# Threeno_Tiny_Tx_Rev1B.net
KiCad netlist of a schematic drawn in EAGLE
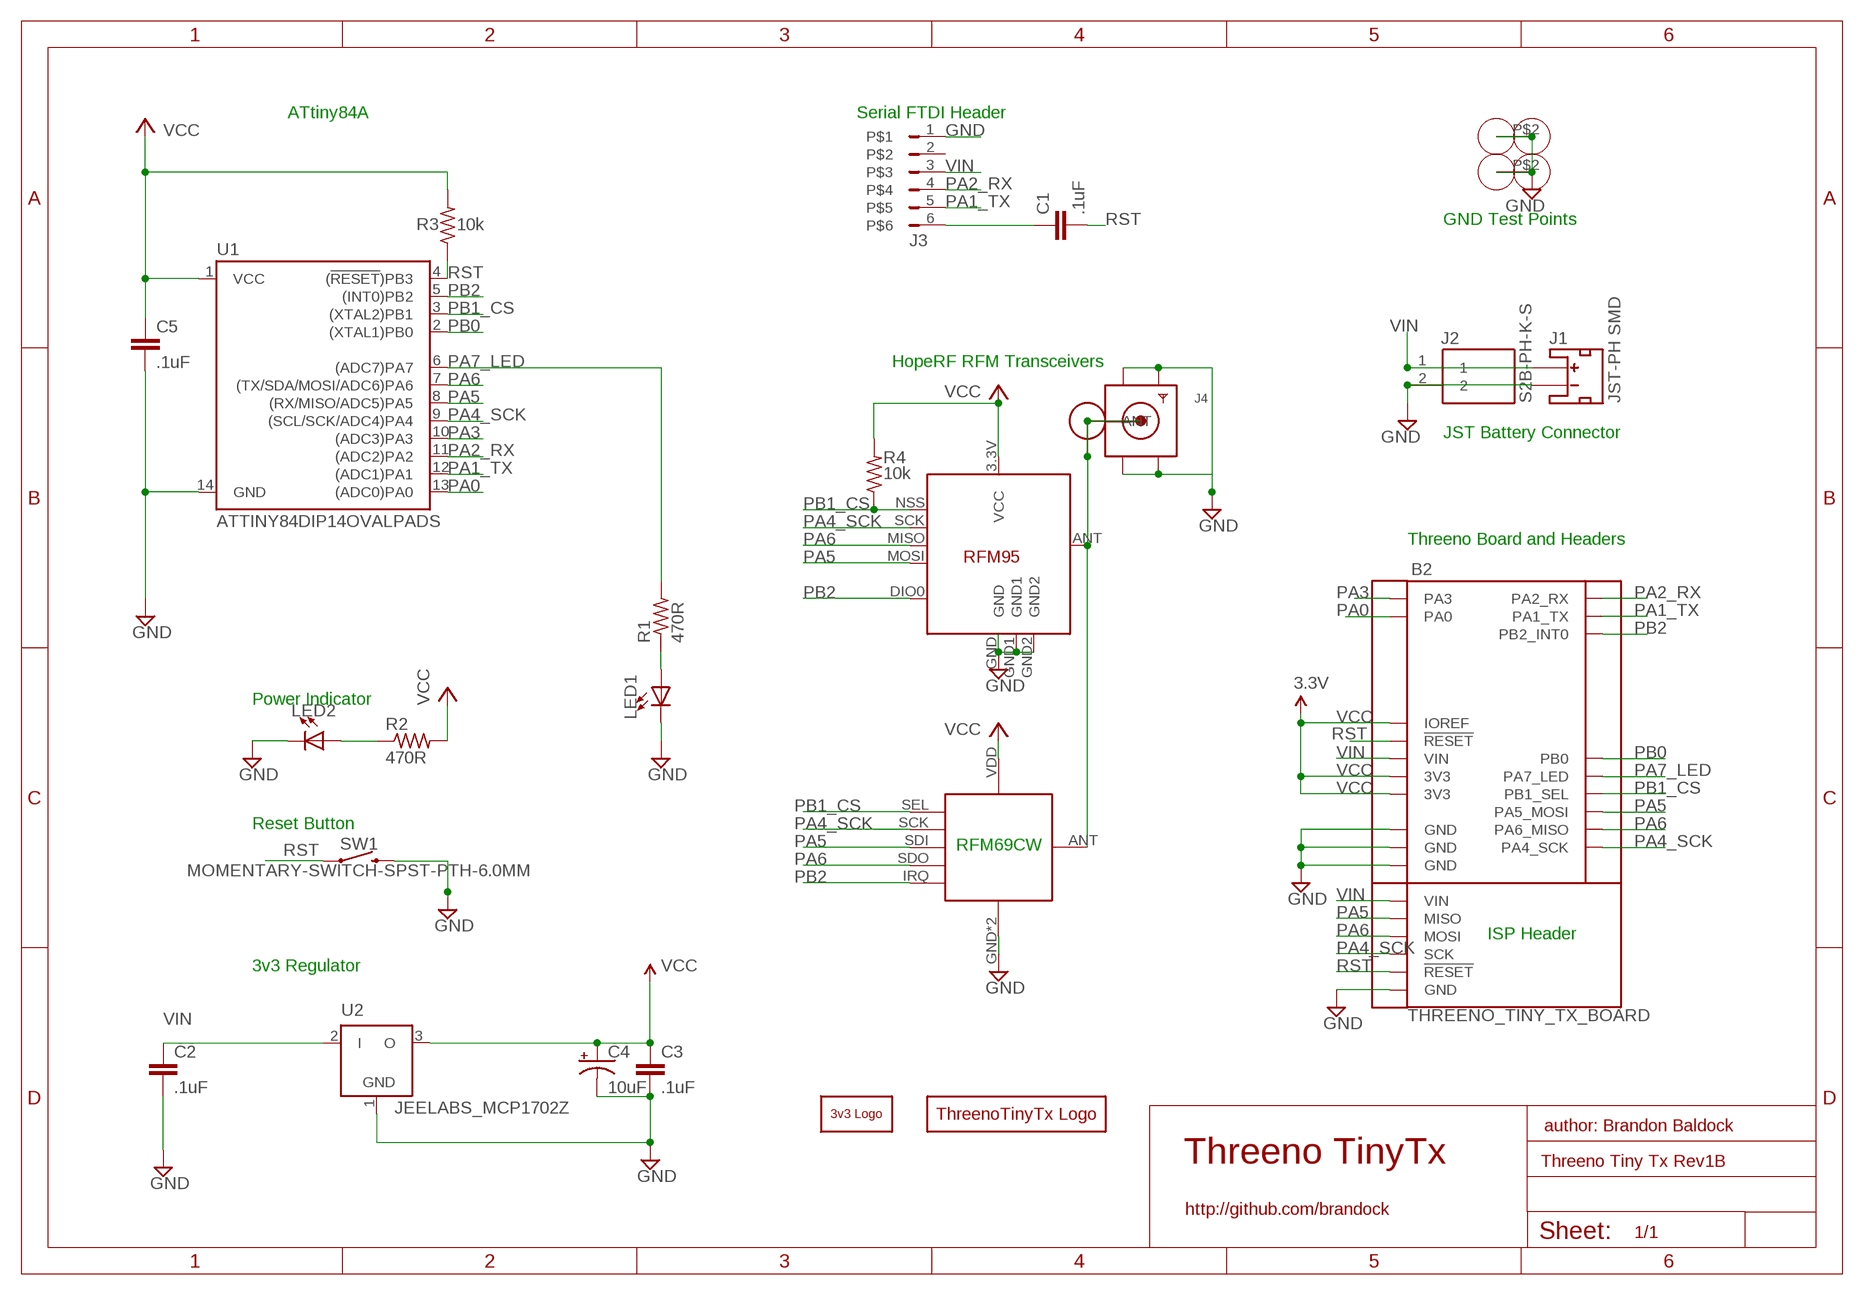
[diagram p0: schematic, sheet 1]

(export (version "E")
  (design (tool "Eeschema 10.0.6"))
  (components
    (comp (ref "B1")
      (value "3VTHREENO_BOTTOM_SILK")
      (footprint "eagle-import:3VTHREENO_BOTTOM_SILK")
      (libsource (lib "eagle-import") (part "3VTHREENO_BOTTOM_SILK"))
    )
    (comp (ref "B2")
      (value "THREENO_TINY_TX_BOARD")
      (footprint "eagle-import:THREENO_TINY_TX_BOARD")
      (libsource (lib "eagle-import") (part "THREENO_TINY_TX_BOARD"))
    )
    (comp (ref "B3")
      (value "THREENO_TINY_TX_LOGOTHREENO_TINY_TX_LOGO")
      (footprint "eagle-import:THREENO_TINY_TX_LOGO")
      (libsource (lib "eagle-import") (part "THREENO_TINY_TX_LOGOTHREENO_TINY_TX_LOGO"))
    )
    (comp (ref "C1")
      (value ".1uF")
      (footprint "eagle-import:C025-024X044-NO-MIDDLE-SILK")
      (libsource (lib "eagle-import") (part "C-EU025-024X044-NO_MIDDLE_SILK"))
    )
    (comp (ref "C2")
      (value ".1uF")
      (footprint "eagle-import:C025-024X044-NO-MIDDLE-SILK")
      (libsource (lib "eagle-import") (part "C-EU025-024X044-NO_MIDDLE_SILK"))
    )
    (comp (ref "C3")
      (value ".1uF")
      (footprint "eagle-import:C025-024X044-NO-MIDDLE-SILK")
      (libsource (lib "eagle-import") (part "C-EU025-024X044-NO_MIDDLE_SILK"))
    )
    (comp (ref "C4")
      (value "10uF")
      (footprint "eagle-import:E1,8-4")
      (libsource (lib "eagle-import") (part "CPOL-USE1.8-4"))
    )
    (comp (ref "C5")
      (value ".1uF")
      (footprint "eagle-import:C025-024X044-NO-MIDDLE-SILK")
      (libsource (lib "eagle-import") (part "C-EU025-024X044-NO_MIDDLE_SILK"))
    )
    (comp (ref "J1")
      (value "JST_2MM_MALE")
      (footprint "eagle-import:JST-2-SMD")
      (libsource (lib "eagle-import") (part "JST_2MM_MALE"))
    )
    (comp (ref "J2")
      (value "S2B-PH-K-S")
      (footprint "eagle-import:S2BPHKS")
      (libsource (lib "eagle-import") (part "S2B-PH-K-S"))
    )
    (comp (ref "J3")
      (value "FTDI")
      (footprint "eagle-import:FTDI_ROUND_HEADER_SILK")
      (libsource (lib "eagle-import") (part "FTDI"))
    )
    (comp (ref "J4")
      (value "SMACONNECTOR_EDGE")
      (footprint "eagle-import:SMA_EDGELAUNCH")
      (libsource (lib "eagle-import") (part "SMACONNECTOR_EDGE"))
    )
    (comp (ref "J5")
      (value "RFM12B_ANTENNA")
      (footprint "eagle-import:RFM12B-ANTENNA")
      (libsource (lib "eagle-import") (part "RFM12B_ANTENNA"))
    )
    (comp (ref "J6")
      (value "ALLIGATORCLIP-WIRELOOPTESTPOINT-WIRELOOP")
      (footprint "eagle-import:ALLIGATORCLIP-WIRELOOP")
      (libsource (lib "eagle-import") (part "ALLIGATORCLIP-WIRELOOPTESTPOINT-WIRELOOP"))
    )
    (comp (ref "J7")
      (value "ALLIGATORCLIP-WIRELOOPTESTPOINT-WIRELOOP")
      (footprint "eagle-import:ALLIGATORCLIP-WIRELOOP")
      (libsource (lib "eagle-import") (part "ALLIGATORCLIP-WIRELOOPTESTPOINT-WIRELOOP"))
    )
    (comp (ref "LED1")
      (value "LED-BRANDOCK3MM")
      (footprint "eagle-import:LED3MM-BRANDOCK")
      (libsource (lib "eagle-import") (part "LED-BRANDOCK3MM"))
    )
    (comp (ref "LED2")
      (value "LED-BRANDOCK3MM")
      (footprint "eagle-import:LED3MM-BRANDOCK")
      (libsource (lib "eagle-import") (part "LED-BRANDOCK3MM"))
    )
    (comp (ref "R1")
      (value "470R")
      (footprint "eagle-import:0204_7")
      (libsource (lib "eagle-import") (part "R-US_0204/7"))
    )
    (comp (ref "R2")
      (value "470R")
      (footprint "eagle-import:0204_7")
      (libsource (lib "eagle-import") (part "R-US_0204/7"))
    )
    (comp (ref "R3")
      (value "10k")
      (footprint "eagle-import:0204_7")
      (libsource (lib "eagle-import") (part "R-US_0204/7"))
    )
    (comp (ref "R4")
      (value "10k")
      (footprint "eagle-import:0204_7")
      (libsource (lib "eagle-import") (part "R-US_0204/7"))
    )
    (comp (ref "RF1")
      (value "RFM12B_MINPADS")
      (footprint "eagle-import:RFM12B-MINPADS")
      (libsource (lib "eagle-import") (part "RFM12B_MINPADS"))
    )
    (comp (ref "RF2")
      (value "RFM95LONGER")
      (footprint "eagle-import:RFM95_LONGER")
      (libsource (lib "eagle-import") (part "RFM95LONGER"))
    )
    (comp (ref "SW1")
      (value "MOMENTARY-SWITCH-SPST-PTH-6.0MM")
      (footprint "eagle-import:TACTILE_SWITCH_PTH_6.0MM")
      (libsource (lib "eagle-import") (part "MOMENTARY-SWITCH-SPST-PTH-6.0MM"))
    )
    (comp (ref "U1")
      (value "ATTINY84DIP14OVALPADS")
      (footprint "eagle-import:DIP14-OVALPADS")
      (libsource (lib "eagle-import") (part "ATTINY84DIP14OVALPADS"))
    )
    (comp (ref "U2")
      (value "JEELABS_MCP1702Z")
      (footprint "eagle-import:JEELABS_TO92")
      (libsource (lib "eagle-import") (part "JEELABS_MCP1702Z"))
    )
  )
  (nets
    (net (code "1") (name "/PA0") (class "Default")
      (node (ref "B2") (pin "PA0") (pinfunction "PA0_PA0") (pintype "bidirectional"))
      (node (ref "U1") (pin "13") (pinfunction "(ADC0)PA0_13") (pintype "bidirectional"))
    )
    (net (code "2") (name "/PA1_TX") (class "Default")
      (node (ref "B2") (pin "PA1") (pinfunction "PA1_TX_PA1") (pintype "bidirectional"))
      (node (ref "J3") (pin "5") (pinfunction "P$5_5") (pintype "bidirectional"))
      (node (ref "U1") (pin "12") (pinfunction "(ADC1)PA1_12") (pintype "bidirectional"))
    )
    (net (code "3") (name "/PA2_RX") (class "Default")
      (node (ref "B2") (pin "PA2") (pinfunction "PA2_RX_PA2") (pintype "bidirectional"))
      (node (ref "J3") (pin "4") (pinfunction "P$4_4") (pintype "bidirectional"))
      (node (ref "U1") (pin "11") (pinfunction "(ADC2)PA2_11") (pintype "bidirectional"))
    )
    (net (code "4") (name "/PA3") (class "Default")
      (node (ref "B2") (pin "PA3") (pinfunction "PA3_PA3") (pintype "bidirectional"))
      (node (ref "U1") (pin "10") (pinfunction "(ADC3)PA3_10") (pintype "bidirectional"))
    )
    (net (code "5") (name "/PA4_SCK") (class "Default")
      (node (ref "B2") (pin "PA4") (pinfunction "PA4_SCK_PA4") (pintype "bidirectional"))
      (node (ref "B2") (pin "SCK@ICSP") (pinfunction "SCK_SCK@ICSP") (pintype "bidirectional"))
      (node (ref "RF1") (pin "SCK") (pinfunction "SCK_SCK") (pintype "bidirectional"))
      (node (ref "RF2") (pin "SCK") (pinfunction "SCK_SCK") (pintype "input"))
      (node (ref "U1") (pin "9") (pinfunction "(SCL/SCK/ADC4)PA4_9") (pintype "bidirectional"))
    )
    (net (code "6") (name "/PA5") (class "Default")
      (node (ref "B2") (pin "MISO@ICSP") (pinfunction "MISO_MISO@ICSP") (pintype "bidirectional"))
      (node (ref "B2") (pin "PA5") (pinfunction "PA5_MOSI_PA5") (pintype "bidirectional"))
      (node (ref "RF1") (pin "SDI") (pinfunction "SDI/MOSI_SDI") (pintype "bidirectional"))
      (node (ref "RF2") (pin "MOSI") (pinfunction "MOSI_MOSI") (pintype "output"))
      (node (ref "U1") (pin "8") (pinfunction "(RX/MISO/ADC5)PA5_8") (pintype "bidirectional"))
    )
    (net (code "7") (name "/PA6") (class "Default")
      (node (ref "B2") (pin "MOSI@ICSP") (pinfunction "MOSI_MOSI@ICSP") (pintype "bidirectional"))
      (node (ref "B2") (pin "PA6") (pinfunction "PA6_MISO_PA6") (pintype "bidirectional"))
      (node (ref "RF1") (pin "SDO") (pinfunction "SDO/MISO_SDO") (pintype "bidirectional"))
      (node (ref "RF2") (pin "MISO") (pinfunction "MISO_MISO") (pintype "input"))
      (node (ref "U1") (pin "7") (pinfunction "(TX/SDA/MOSI/ADC6)PA6_7") (pintype "bidirectional"))
    )
    (net (code "8") (name "/PA7_LED") (class "Default")
      (node (ref "B2") (pin "PA7") (pinfunction "PA7_LED_PA7") (pintype "bidirectional"))
      (node (ref "R1") (pin "2") (pinfunction "2_2") (pintype "passive"))
      (node (ref "U1") (pin "6") (pinfunction "(ADC7)PA7_6") (pintype "bidirectional"))
    )
    (net (code "9") (name "/PB0") (class "Default")
      (node (ref "B2") (pin "PB0") (pinfunction "PB0_PB0") (pintype "bidirectional"))
      (node (ref "U1") (pin "2") (pinfunction "(XTAL1)PB0_2") (pintype "bidirectional"))
    )
    (net (code "10") (name "/PB1_CS") (class "Default")
      (node (ref "B2") (pin "PB1") (pinfunction "PB1_SEL_PB1") (pintype "bidirectional"))
      (node (ref "R4") (pin "1") (pinfunction "1_1") (pintype "passive"))
      (node (ref "RF1") (pin "SEL") (pinfunction "SEL_SEL") (pintype "bidirectional"))
      (node (ref "RF2") (pin "NSS") (pinfunction "SEL_NSS") (pintype "input"))
      (node (ref "U1") (pin "3") (pinfunction "(XTAL2)PB1_3") (pintype "bidirectional"))
    )
    (net (code "11") (name "/PB2") (class "Default")
      (node (ref "B2") (pin "PB2") (pinfunction "PB2_INT0_PB2") (pintype "bidirectional"))
      (node (ref "RF1") (pin "IRQ") (pinfunction "IRQ_IRQ") (pintype "bidirectional"))
      (node (ref "RF2") (pin "DIO0") (pinfunction "DIO0_DIO0") (pintype "open_collector"))
      (node (ref "U1") (pin "5") (pinfunction "(INT0)PB2_5") (pintype "bidirectional"))
    )
    (net (code "12") (name "/RST") (class "Default")
      (node (ref "B2") (pin "!RESET!") (pinfunction "~{RESET}_!RESET!") (pintype "bidirectional"))
      (node (ref "B2") (pin "RESET@ICSP") (pinfunction "~{RESET}_RESET@ICSP") (pintype "bidirectional"))
      (node (ref "C1") (pin "2") (pinfunction "2_2") (pintype "passive"))
      (node (ref "R3") (pin "1") (pinfunction "1_1") (pintype "passive"))
      (node (ref "SW1") (pin "1") (pinfunction "1_1") (pintype "passive"))
      (node (ref "U1") (pin "4") (pinfunction "(~{RESET})PB3_4") (pintype "bidirectional"))
    )
    (net (code "13") (name "/VIN") (class "Default")
      (node (ref "B2") (pin "VIN") (pinfunction "VIN_VIN") (pintype "bidirectional"))
      (node (ref "B2") (pin "VIN@ICSP") (pinfunction "VIN_VIN@ICSP") (pintype "bidirectional"))
      (node (ref "C2") (pin "1") (pinfunction "1_1") (pintype "passive"))
      (node (ref "J1") (pin "2") (pinfunction "+_2") (pintype "bidirectional"))
      (node (ref "J2") (pin "1") (pinfunction "1_1") (pintype "bidirectional"))
      (node (ref "J3") (pin "3") (pinfunction "P$3_3") (pintype "bidirectional"))
      (node (ref "U2") (pin "2") (pinfunction "I_2") (pintype "input"))
    )
    (net (code "14") (name "3.3V") (class "Default")
      (node (ref "B2") (pin "3.3V") (pinfunction "3V3_3.3V") (pintype "bidirectional"))
      (node (ref "B2") (pin "3.3V@2") (pinfunction "3V3_3.3V@2") (pintype "bidirectional"))
      (node (ref "B2") (pin "IOREF") (pinfunction "IOREF_IOREF") (pintype "bidirectional"))
      (node (ref "C3") (pin "1") (pinfunction "1_1") (pintype "passive"))
      (node (ref "C4") (pin "+") (pinfunction "+_+") (pintype "passive"))
      (node (ref "C5") (pin "1") (pinfunction "1_1") (pintype "passive"))
      (node (ref "R2") (pin "2") (pinfunction "2_2") (pintype "passive"))
      (node (ref "R3") (pin "2") (pinfunction "2_2") (pintype "passive"))
      (node (ref "R4") (pin "2") (pinfunction "2_2") (pintype "passive"))
      (node (ref "RF1") (pin "VDD") (pinfunction "VDD_VDD") (pintype "bidirectional"))
      (node (ref "RF2") (pin "3.3V") (pinfunction "VCC_3.3V") (pintype "power_in"))
      (node (ref "U1") (pin "1") (pinfunction "VCC_1") (pintype "bidirectional"))
      (node (ref "U2") (pin "3") (pinfunction "O_3") (pintype "input"))
    )
    (net (code "15") (name "GND") (class "Default")
      (node (ref "B2") (pin "GND@1") (pinfunction "GND_GND@1") (pintype "bidirectional"))
      (node (ref "B2") (pin "GND@2") (pinfunction "GND_GND@2") (pintype "bidirectional"))
      (node (ref "B2") (pin "GND@3") (pinfunction "GND_GND@3") (pintype "bidirectional"))
      (node (ref "B2") (pin "GND@ICSP") (pinfunction "GND_GND@ICSP") (pintype "bidirectional"))
      (node (ref "C2") (pin "2") (pinfunction "2_2") (pintype "passive"))
      (node (ref "C3") (pin "2") (pinfunction "2_2") (pintype "passive"))
      (node (ref "C4") (pin "-") (pinfunction "-_-") (pintype "passive"))
      (node (ref "C5") (pin "2") (pinfunction "2_2") (pintype "passive"))
      (node (ref "J1") (pin "1") (pinfunction "-_1") (pintype "bidirectional"))
      (node (ref "J2") (pin "2") (pinfunction "2_2") (pintype "bidirectional"))
      (node (ref "J3") (pin "1") (pinfunction "P$1_1") (pintype "bidirectional"))
      (node (ref "J4") (pin "GND@1") (pinfunction "GND4_GND@1") (pintype "power_in"))
      (node (ref "J4") (pin "GND@2") (pinfunction "GND3_GND@2") (pintype "power_in"))
      (node (ref "J4") (pin "GND@3") (pinfunction "GND2_GND@3") (pintype "power_in"))
      (node (ref "J4") (pin "GND@4") (pinfunction "GND1_GND@4") (pintype "power_in"))
      (node (ref "J6") (pin "P$1") (pinfunction "P$1_P$1") (pintype "bidirectional"))
      (node (ref "J6") (pin "P$2") (pinfunction "P$2_P$2") (pintype "bidirectional"))
      (node (ref "J7") (pin "P$1") (pinfunction "P$1_P$1") (pintype "bidirectional"))
      (node (ref "J7") (pin "P$2") (pinfunction "P$2_P$2") (pintype "bidirectional"))
      (node (ref "LED1") (pin "K") (pinfunction "C_K") (pintype "passive"))
      (node (ref "LED2") (pin "K") (pinfunction "C_K") (pintype "passive"))
      (node (ref "RF1") (pin "GND") (pinfunction "GND_GND") (pintype "bidirectional"))
      (node (ref "RF1") (pin "GND2") (pinfunction "GND_GND2") (pintype "bidirectional"))
      (node (ref "RF2") (pin "GND") (pinfunction "GND_GND") (pintype "power_in"))
      (node (ref "RF2") (pin "GND1") (pinfunction "GND1_GND1") (pintype "power_in"))
      (node (ref "RF2") (pin "GND2") (pinfunction "GND2_GND2") (pintype "power_in"))
      (node (ref "SW1") (pin "3") (pinfunction "2_3") (pintype "passive"))
      (node (ref "U1") (pin "14") (pinfunction "GND_14") (pintype "bidirectional"))
      (node (ref "U2") (pin "1") (pinfunction "GND_1") (pintype "power_in"))
    )
    (net (code "16") (name "Net-(J3-P$6)") (class "Default")
      (node (ref "C1") (pin "1") (pinfunction "1_1") (pintype "passive"))
      (node (ref "J3") (pin "6") (pinfunction "P$6_6") (pintype "bidirectional"))
    )
    (net (code "17") (name "Net-(J4-ANT)") (class "Default")
      (node (ref "J4") (pin "P") (pinfunction "ANT_P") (pintype "bidirectional"))
      (node (ref "J5") (pin "P$1") (pinfunction "1_P$1") (pintype "bidirectional"))
      (node (ref "RF1") (pin "ANT") (pinfunction "ANT_ANT") (pintype "bidirectional"))
      (node (ref "RF2") (pin "ANT") (pinfunction "ANT_ANT") (pintype "passive"))
    )
    (net (code "18") (name "Net-(LED1-PadA)") (class "Default")
      (node (ref "LED1") (pin "A") (pinfunction "A_A") (pintype "passive"))
      (node (ref "R1") (pin "1") (pinfunction "1_1") (pintype "passive"))
    )
    (net (code "19") (name "Net-(LED2-PadA)") (class "Default")
      (node (ref "LED2") (pin "A") (pinfunction "A_A") (pintype "passive"))
      (node (ref "R2") (pin "1") (pinfunction "1_1") (pintype "passive"))
    )
    (net (code "20") (name "unconnected-(J1-PAD1-PadNC1)") (class "Default")
      (node (ref "J1") (pin "NC1") (pinfunction "PAD1_NC1") (pintype "bidirectional"))
    )
    (net (code "21") (name "unconnected-(J1-PAD2-PadNC2)") (class "Default")
      (node (ref "J1") (pin "NC2") (pinfunction "PAD2_NC2") (pintype "bidirectional"))
    )
    (net (code "22") (name "unconnected-(J3-P$2-Pad2)") (class "Default")
      (node (ref "J3") (pin "2") (pinfunction "P$2_2") (pintype "bidirectional"))
    )
  )
)
